# LEDs.net
KiCad netlist of a schematic drawn in Altium Designer
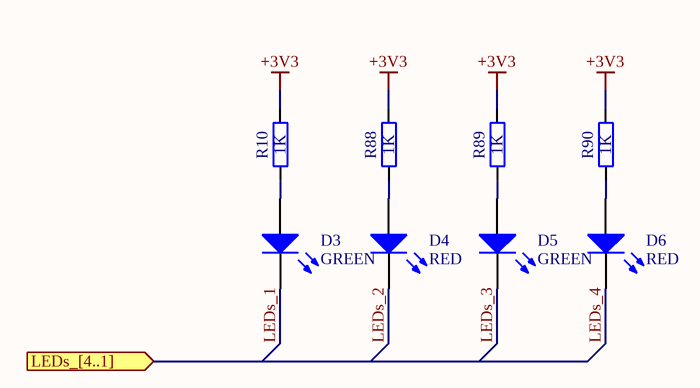
[diagram p0: LEDs.SchDoc]

(export (version "E")
  (design (tool "Eeschema 10.0.6"))
  (components
    (comp (ref "D3")
      (value "GREEN")
      (footprint "LED_0603_APT1608")
      (libsource (lib "DSO") (part "LED GREEN 0603 APT1608"))
    )
    (comp (ref "D4")
      (value "RED")
      (footprint "LED_0603_APT1608")
      (libsource (lib "DSO") (part "LED RED 0603 APT1608"))
    )
    (comp (ref "D5")
      (value "GREEN")
      (footprint "LED_0603_APT1608")
      (libsource (lib "DSO") (part "LED GREEN 0603 APT1608"))
    )
    (comp (ref "D6")
      (value "RED")
      (footprint "LED_0603_APT1608")
      (libsource (lib "DSO") (part "LED RED 0603 APT1608"))
    )
    (comp (ref "R10")
      (value "1K")
      (footprint "GEN_R_0402")
      (fields (field (name "TOLERANCE") "1%"))
      (libsource (lib "DSO") (part "RES 1K OHM 1% 1/10W 0402"))
    )
    (comp (ref "R88")
      (value "1K")
      (footprint "GEN_R_0402")
      (fields (field (name "TOLERANCE") "1%"))
      (libsource (lib "DSO") (part "RES 1K OHM 1% 1/10W 0402"))
    )
    (comp (ref "R89")
      (value "1K")
      (footprint "GEN_R_0402")
      (fields (field (name "TOLERANCE") "1%"))
      (libsource (lib "DSO") (part "RES 1K OHM 1% 1/10W 0402"))
    )
    (comp (ref "R90")
      (value "1K")
      (footprint "GEN_R_0402")
      (fields (field (name "TOLERANCE") "1%"))
      (libsource (lib "DSO") (part "RES 1K OHM 1% 1/10W 0402"))
    )
  )
  (nets
    (net (code "1") (name "+3V3") (class "Default")
      (node (ref "R10") (pin "2") (pinfunction "2_2") (pintype "passive"))
      (node (ref "R88") (pin "2") (pinfunction "2_2") (pintype "passive"))
      (node (ref "R89") (pin "2") (pinfunction "2_2") (pintype "passive"))
      (node (ref "R90") (pin "2") (pinfunction "2_2") (pintype "passive"))
    )
    (net (code "2") (name "/LEDs_1") (class "Default")
      (node (ref "D3") (pin "1") (pinfunction "K_1") (pintype "passive"))
    )
    (net (code "3") (name "/LEDs_2") (class "Default")
      (node (ref "D4") (pin "1") (pinfunction "K_1") (pintype "passive"))
    )
    (net (code "4") (name "/LEDs_3") (class "Default")
      (node (ref "D5") (pin "1") (pinfunction "K_1") (pintype "passive"))
    )
    (net (code "5") (name "/LEDs_4") (class "Default")
      (node (ref "D6") (pin "1") (pinfunction "K_1") (pintype "passive"))
    )
    (net (code "7") (name "Net-(D3-A)") (class "Default")
      (node (ref "D3") (pin "2") (pinfunction "A_2") (pintype "passive"))
      (node (ref "R10") (pin "1") (pinfunction "1_1") (pintype "passive"))
    )
    (net (code "8") (name "Net-(D4-A)") (class "Default")
      (node (ref "D4") (pin "2") (pinfunction "A_2") (pintype "passive"))
      (node (ref "R88") (pin "1") (pinfunction "1_1") (pintype "passive"))
    )
    (net (code "9") (name "Net-(D5-A)") (class "Default")
      (node (ref "D5") (pin "2") (pinfunction "A_2") (pintype "passive"))
      (node (ref "R89") (pin "1") (pinfunction "1_1") (pintype "passive"))
    )
    (net (code "10") (name "Net-(D6-A)") (class "Default")
      (node (ref "D6") (pin "2") (pinfunction "A_2") (pintype "passive"))
      (node (ref "R90") (pin "1") (pinfunction "1_1") (pintype "passive"))
    )
  )
)
